# 1-BitSelect.net
KiCad netlist of a schematic drawn in EAGLE
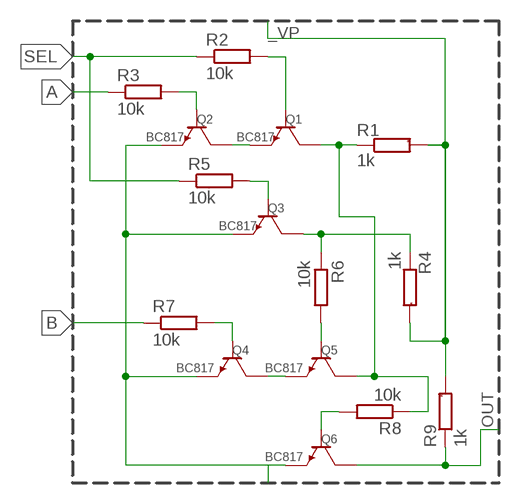
[diagram p0: schematic, sheet 1]

(export (version "E")
  (design (tool "Eeschema 10.0.6"))
  (components
    (comp (ref "Q1")
      (value "BC817")
      (footprint "eagle-import:SOT23")
      (libsource (lib "eagle-import") (part "TRANSISTOR-NPN-GENERIC-SOT23-BECDEFAULT"))
    )
    (comp (ref "Q2")
      (value "BC817")
      (footprint "eagle-import:SOT23")
      (libsource (lib "eagle-import") (part "TRANSISTOR-NPN-GENERIC-SOT23-BECDEFAULT"))
    )
    (comp (ref "Q3")
      (value "BC817")
      (footprint "eagle-import:SOT23")
      (libsource (lib "eagle-import") (part "TRANSISTOR-NPN-GENERIC-SOT23-BECDEFAULT"))
    )
    (comp (ref "Q4")
      (value "BC817")
      (footprint "eagle-import:SOT23")
      (libsource (lib "eagle-import") (part "TRANSISTOR-NPN-GENERIC-SOT23-BECDEFAULT"))
    )
    (comp (ref "Q5")
      (value "BC817")
      (footprint "eagle-import:SOT23")
      (libsource (lib "eagle-import") (part "TRANSISTOR-NPN-GENERIC-SOT23-BECDEFAULT"))
    )
    (comp (ref "Q6")
      (value "BC817")
      (footprint "eagle-import:SOT23")
      (libsource (lib "eagle-import") (part "TRANSISTOR-NPN-GENERIC-SOT23-BECDEFAULT"))
    )
    (comp (ref "R1")
      (value "1k")
      (footprint "eagle-import:R0603-MARK")
      (libsource (lib "eagle-import") (part "R-EU-MARKEDR0603"))
    )
    (comp (ref "R2")
      (value "10k")
      (footprint "eagle-import:R0603")
      (libsource (lib "eagle-import") (part "R-EU_R0603"))
    )
    (comp (ref "R3")
      (value "10k")
      (footprint "eagle-import:R0603")
      (libsource (lib "eagle-import") (part "R-EU_R0603"))
    )
    (comp (ref "R4")
      (value "1k")
      (footprint "eagle-import:R0603-MARK")
      (libsource (lib "eagle-import") (part "R-EU-MARKEDR0603"))
    )
    (comp (ref "R5")
      (value "10k")
      (footprint "eagle-import:R0603")
      (libsource (lib "eagle-import") (part "R-EU_R0603"))
    )
    (comp (ref "R6")
      (value "10k")
      (footprint "eagle-import:R0603")
      (libsource (lib "eagle-import") (part "R-EU_R0603"))
    )
    (comp (ref "R7")
      (value "10k")
      (footprint "eagle-import:R0603")
      (libsource (lib "eagle-import") (part "R-EU_R0603"))
    )
    (comp (ref "R8")
      (value "10k")
      (footprint "eagle-import:R0603")
      (libsource (lib "eagle-import") (part "R-EU_R0603"))
    )
    (comp (ref "R9")
      (value "1k")
      (footprint "eagle-import:R0603-MARK")
      (libsource (lib "eagle-import") (part "R-EU-MARKEDR0603"))
    )
  )
  (nets
    (net (code "1") (name "/OUT") (class "Default")
      (node (ref "Q6") (pin "P$3") (pinfunction "COLLECTOR_P$3") (pintype "bidirectional"))
      (node (ref "R9") (pin "1") (pinfunction "1_1") (pintype "passive"))
    )
    (net (code "2") (name "/_VP") (class "Default")
      (node (ref "R1") (pin "2") (pinfunction "2_2") (pintype "passive"))
      (node (ref "R4") (pin "2") (pinfunction "2_2") (pintype "passive"))
      (node (ref "R9") (pin "2") (pinfunction "2_2") (pintype "passive"))
    )
    (net (code "3") (name "A") (class "Default")
      (node (ref "R3") (pin "1") (pinfunction "1_1") (pintype "passive"))
    )
    (net (code "4") (name "B") (class "Default")
      (node (ref "R7") (pin "1") (pinfunction "1_1") (pintype "passive"))
    )
    (net (code "5") (name "Net-(Q1-BASE)") (class "Default")
      (node (ref "Q1") (pin "P$1") (pinfunction "BASE_P$1") (pintype "bidirectional"))
      (node (ref "R2") (pin "2") (pinfunction "2_2") (pintype "passive"))
    )
    (net (code "6") (name "Net-(Q1-COLLECTOR)") (class "Default")
      (node (ref "Q1") (pin "P$3") (pinfunction "COLLECTOR_P$3") (pintype "bidirectional"))
      (node (ref "Q5") (pin "P$3") (pinfunction "COLLECTOR_P$3") (pintype "bidirectional"))
      (node (ref "R1") (pin "1") (pinfunction "1_1") (pintype "passive"))
      (node (ref "R8") (pin "1") (pinfunction "1_1") (pintype "passive"))
    )
    (net (code "7") (name "Net-(Q1-EMITTER)") (class "Default")
      (node (ref "Q1") (pin "P$2") (pinfunction "EMITTER_P$2") (pintype "bidirectional"))
      (node (ref "Q2") (pin "P$3") (pinfunction "COLLECTOR_P$3") (pintype "bidirectional"))
    )
    (net (code "8") (name "Net-(Q2-BASE)") (class "Default")
      (node (ref "Q2") (pin "P$1") (pinfunction "BASE_P$1") (pintype "bidirectional"))
      (node (ref "R3") (pin "2") (pinfunction "2_2") (pintype "passive"))
    )
    (net (code "9") (name "Net-(Q2-EMITTER)") (class "Default")
      (node (ref "Q2") (pin "P$2") (pinfunction "EMITTER_P$2") (pintype "bidirectional"))
      (node (ref "Q3") (pin "P$2") (pinfunction "EMITTER_P$2") (pintype "bidirectional"))
      (node (ref "Q4") (pin "P$2") (pinfunction "EMITTER_P$2") (pintype "bidirectional"))
      (node (ref "Q6") (pin "P$2") (pinfunction "EMITTER_P$2") (pintype "bidirectional"))
    )
    (net (code "10") (name "Net-(Q3-BASE)") (class "Default")
      (node (ref "Q3") (pin "P$1") (pinfunction "BASE_P$1") (pintype "bidirectional"))
      (node (ref "R5") (pin "2") (pinfunction "2_2") (pintype "passive"))
    )
    (net (code "11") (name "Net-(Q3-COLLECTOR)") (class "Default")
      (node (ref "Q3") (pin "P$3") (pinfunction "COLLECTOR_P$3") (pintype "bidirectional"))
      (node (ref "R4") (pin "1") (pinfunction "1_1") (pintype "passive"))
      (node (ref "R6") (pin "1") (pinfunction "1_1") (pintype "passive"))
    )
    (net (code "12") (name "Net-(Q4-BASE)") (class "Default")
      (node (ref "Q4") (pin "P$1") (pinfunction "BASE_P$1") (pintype "bidirectional"))
      (node (ref "R7") (pin "2") (pinfunction "2_2") (pintype "passive"))
    )
    (net (code "13") (name "Net-(Q4-COLLECTOR)") (class "Default")
      (node (ref "Q4") (pin "P$3") (pinfunction "COLLECTOR_P$3") (pintype "bidirectional"))
      (node (ref "Q5") (pin "P$2") (pinfunction "EMITTER_P$2") (pintype "bidirectional"))
    )
    (net (code "14") (name "Net-(Q5-BASE)") (class "Default")
      (node (ref "Q5") (pin "P$1") (pinfunction "BASE_P$1") (pintype "bidirectional"))
      (node (ref "R6") (pin "2") (pinfunction "2_2") (pintype "passive"))
    )
    (net (code "15") (name "Net-(Q6-BASE)") (class "Default")
      (node (ref "Q6") (pin "P$1") (pinfunction "BASE_P$1") (pintype "bidirectional"))
      (node (ref "R8") (pin "2") (pinfunction "2_2") (pintype "passive"))
    )
    (net (code "16") (name "SEL") (class "Default")
      (node (ref "R2") (pin "1") (pinfunction "1_1") (pintype "passive"))
      (node (ref "R5") (pin "1") (pinfunction "1_1") (pintype "passive"))
    )
  )
)
